# power.net
KiCad netlist of a schematic drawn in Altium Designer
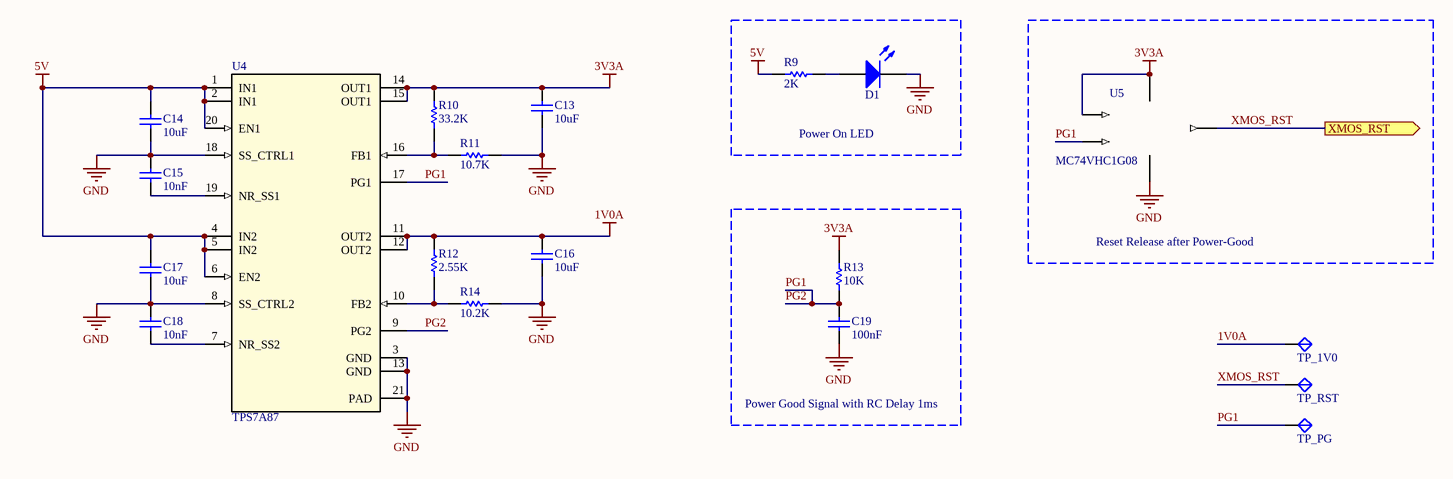
[diagram p0: power.SchDoc]

(export (version "E")
  (design (tool "Eeschema 10.0.6"))
  (components
    (comp (ref "C13")
      (value "10uF")
      (footprint "CAP_0603")
      (description "Multilayer Ceramic Capacitors")
      (fields (field (name "TOLERANCE") "10%") (field (name "Comment") "MLCC"))
      (libsource (lib "Capacitors") (part "MLCC"))
    )
    (comp (ref "C14")
      (value "10uF")
      (footprint "CAP_0603")
      (description "Multilayer Ceramic Capacitors")
      (fields (field (name "TOLERANCE") "10%") (field (name "Comment") "MLCC"))
      (libsource (lib "Capacitors") (part "MLCC"))
    )
    (comp (ref "C15")
      (value "10nF")
      (footprint "CAP_0603")
      (description "Multilayer Ceramic Capacitors")
      (fields (field (name "TOLERANCE") "10%") (field (name "Comment") "MLCC"))
      (libsource (lib "Capacitors") (part "MLCC"))
    )
    (comp (ref "C16")
      (value "10uF")
      (footprint "CAP_0603")
      (description "Multilayer Ceramic Capacitors")
      (fields (field (name "TOLERANCE") "10%") (field (name "Comment") "MLCC"))
      (libsource (lib "Capacitors") (part "MLCC"))
    )
    (comp (ref "C17")
      (value "10uF")
      (footprint "CAP_0603")
      (description "Multilayer Ceramic Capacitors")
      (fields (field (name "TOLERANCE") "10%") (field (name "Comment") "MLCC"))
      (libsource (lib "Capacitors") (part "MLCC"))
    )
    (comp (ref "C18")
      (value "10nF")
      (footprint "CAP_0603")
      (description "Multilayer Ceramic Capacitors")
      (fields (field (name "TOLERANCE") "10%") (field (name "Comment") "MLCC"))
      (libsource (lib "Capacitors") (part "MLCC"))
    )
    (comp (ref "C19")
      (value "100nF")
      (footprint "CAP_0603")
      (description "Multilayer Ceramic Capacitors")
      (fields (field (name "TOLERANCE") "10%") (field (name "Comment") "MLCC"))
      (libsource (lib "Capacitors") (part "MLCC"))
    )
    (comp (ref "D1")
      (value "LED")
      (footprint "0603_RED")
      (description "LED Emitters")
      (libsource (lib "Leds") (part "LED"))
    )
    (comp (ref "R9")
      (value "2K")
      (footprint "RC0603N")
      (description "Chip Resistors")
      (fields (field (name "Comment") "RES"))
      (libsource (lib "Resistors") (part "RES"))
    )
    (comp (ref "R10")
      (value "33.2K")
      (footprint "RC0603N")
      (description "Chip Resistors")
      (fields (field (name "Comment") "RES"))
      (libsource (lib "Resistors") (part "RES"))
    )
    (comp (ref "R11")
      (value "10.7K")
      (footprint "RC0603N")
      (description "Chip Resistors")
      (fields (field (name "Comment") "RES"))
      (libsource (lib "Resistors") (part "RES"))
    )
    (comp (ref "R12")
      (value "2.55K")
      (footprint "RC0603N")
      (description "Chip Resistors")
      (fields (field (name "Comment") "RES"))
      (libsource (lib "Resistors") (part "RES"))
    )
    (comp (ref "R13")
      (value "10K")
      (footprint "RC0603N")
      (description "Chip Resistors")
      (fields (field (name "Comment") "RES"))
      (libsource (lib "Resistors") (part "RES"))
    )
    (comp (ref "R14")
      (value "10.2K")
      (footprint "RC0603N")
      (description "Chip Resistors")
      (fields (field (name "Comment") "RES"))
      (libsource (lib "Resistors") (part "RES"))
    )
    (comp (ref "TP_1V0")
      (value "TestPoint")
      (footprint "TESTPOINT(1)")
      (description "Test Point")
      (libsource (lib "Connectors") (part "TestPoint"))
    )
    (comp (ref "TP_PG")
      (value "TestPoint")
      (footprint "TESTPOINT(1)")
      (description "Test Point")
      (libsource (lib "Connectors") (part "TestPoint"))
    )
    (comp (ref "TP_RST")
      (value "TestPoint")
      (footprint "TESTPOINT(1)")
      (description "Test Point")
      (libsource (lib "Connectors") (part "TestPoint"))
    )
    (comp (ref "U4")
      (value "TPS7A87")
      (footprint "RTJ20")
      (description "TPS7A87 Dual, 500-mA, Low-Noise (3.8 μVRMS), LDO Voltage Regulator")
      (fields
        (field (name "MANUFACTURER") "Texas Instruments")
        (field (name "MANUFACTURER_PART_NUMBER") "TPS7A8701RTJR")
        (field (name "COPYRIGHT") "Copyright (C) 2018 Accelerated Designs. All rights reserved")
      )
      (libsource (lib "TI") (part "TPS7A87"))
    )
    (comp (ref "U5")
      (value "MC74VHC1G08")
      (footprint "SC-88A")
      (description "Single 2-Input AND Gate")
      (libsource (lib "ON") (part "MC74VHC1G08"))
    )
  )
  (nets
    (net (code "1") (name "/PG1") (class "Default")
      (node (ref "C19") (pin "2") (pinfunction "2_2") (pintype "passive"))
      (node (ref "R13") (pin "2") (pinfunction "2_2") (pintype "passive"))
      (node (ref "TP_PG") (pin "1") (pinfunction "1_1") (pintype "passive"))
      (node (ref "U4") (pin "17") (pinfunction "PG1_17") (pintype "open_collector"))
      (node (ref "U4") (pin "9") (pinfunction "PG2_9") (pintype "open_collector"))
      (node (ref "U5") (pin "2") (pinfunction "A_2") (pintype "input"))
    )
    (net (code "2") (name "/XMOS_RST") (class "Default")
      (node (ref "TP_RST") (pin "1") (pinfunction "1_1") (pintype "passive"))
      (node (ref "U5") (pin "4") (pinfunction "Y_4") (pintype "output"))
    )
    (net (code "3") (name "1V0A") (class "Default")
      (node (ref "C16") (pin "2") (pinfunction "2_2") (pintype "passive"))
      (node (ref "R12") (pin "2") (pinfunction "2_2") (pintype "passive"))
      (node (ref "TP_1V0") (pin "1") (pinfunction "1_1") (pintype "passive"))
      (node (ref "U4") (pin "11") (pinfunction "OUT2_11") (pintype "power_in"))
      (node (ref "U4") (pin "12") (pinfunction "OUT2_12") (pintype "power_in"))
    )
    (net (code "4") (name "3V3A") (class "Default")
      (node (ref "C13") (pin "2") (pinfunction "2_2") (pintype "passive"))
      (node (ref "R10") (pin "2") (pinfunction "2_2") (pintype "passive"))
      (node (ref "R13") (pin "1") (pinfunction "1_1") (pintype "passive"))
      (node (ref "U4") (pin "14") (pinfunction "OUT1_14") (pintype "power_in"))
      (node (ref "U4") (pin "15") (pinfunction "OUT1_15") (pintype "power_in"))
      (node (ref "U5") (pin "1") (pinfunction "B_1") (pintype "input"))
      (node (ref "U5") (pin "5") (pinfunction "VCC_5") (pintype "passive"))
    )
    (net (code "5") (name "5V") (class "Default")
      (node (ref "C14") (pin "2") (pinfunction "2_2") (pintype "passive"))
      (node (ref "C17") (pin "2") (pinfunction "2_2") (pintype "passive"))
      (node (ref "R9") (pin "2") (pinfunction "2_2") (pintype "passive"))
      (node (ref "U4") (pin "1") (pinfunction "IN1_1") (pintype "power_in"))
      (node (ref "U4") (pin "2") (pinfunction "IN1_2") (pintype "power_in"))
      (node (ref "U4") (pin "20") (pinfunction "EN1_20") (pintype "input"))
      (node (ref "U4") (pin "4") (pinfunction "IN2_4") (pintype "power_in"))
      (node (ref "U4") (pin "5") (pinfunction "IN2_5") (pintype "power_in"))
      (node (ref "U4") (pin "6") (pinfunction "EN2_6") (pintype "input"))
    )
    (net (code "6") (name "GND") (class "Default")
      (node (ref "C13") (pin "1") (pinfunction "1_1") (pintype "passive"))
      (node (ref "C14") (pin "1") (pinfunction "1_1") (pintype "passive"))
      (node (ref "C15") (pin "2") (pinfunction "2_2") (pintype "passive"))
      (node (ref "C16") (pin "1") (pinfunction "1_1") (pintype "passive"))
      (node (ref "C17") (pin "1") (pinfunction "1_1") (pintype "passive"))
      (node (ref "C18") (pin "2") (pinfunction "2_2") (pintype "passive"))
      (node (ref "C19") (pin "1") (pinfunction "1_1") (pintype "passive"))
      (node (ref "D1") (pin "2") (pinfunction "K_2") (pintype "passive"))
      (node (ref "R11") (pin "1") (pinfunction "1_1") (pintype "passive"))
      (node (ref "R14") (pin "1") (pinfunction "1_1") (pintype "passive"))
      (node (ref "U4") (pin "13") (pinfunction "GND_13") (pintype "power_in"))
      (node (ref "U4") (pin "18") (pinfunction "SS_CTRL1_18") (pintype "input"))
      (node (ref "U4") (pin "21") (pinfunction "PAD_21") (pintype "power_in"))
      (node (ref "U4") (pin "3") (pinfunction "GND_3") (pintype "power_in"))
      (node (ref "U4") (pin "8") (pinfunction "SS_CTRL2_8") (pintype "input"))
      (node (ref "U5") (pin "3") (pinfunction "GND_3") (pintype "passive"))
    )
    (net (code "7") (name "Net-(D1-A)") (class "Default")
      (node (ref "D1") (pin "1") (pinfunction "A_1") (pintype "passive"))
      (node (ref "R9") (pin "1") (pinfunction "1_1") (pintype "passive"))
    )
    (net (code "8") (name "Net-(U4-FB1)") (class "Default")
      (node (ref "R10") (pin "1") (pinfunction "1_1") (pintype "passive"))
      (node (ref "R11") (pin "2") (pinfunction "2_2") (pintype "passive"))
      (node (ref "U4") (pin "16") (pinfunction "FB1_16") (pintype "input"))
    )
    (net (code "9") (name "Net-(U4-FB2)") (class "Default")
      (node (ref "R12") (pin "1") (pinfunction "1_1") (pintype "passive"))
      (node (ref "R14") (pin "2") (pinfunction "2_2") (pintype "passive"))
      (node (ref "U4") (pin "10") (pinfunction "FB2_10") (pintype "input"))
    )
    (net (code "10") (name "Net-(U4-NR_SS1)") (class "Default")
      (node (ref "C15") (pin "1") (pinfunction "1_1") (pintype "passive"))
      (node (ref "U4") (pin "19") (pinfunction "NR_SS1_19") (pintype "input"))
    )
    (net (code "11") (name "Net-(U4-NR_SS2)") (class "Default")
      (node (ref "C18") (pin "1") (pinfunction "1_1") (pintype "passive"))
      (node (ref "U4") (pin "7") (pinfunction "NR_SS2_7") (pintype "input"))
    )
  )
)
